# schematics.net
KiCad netlist of a schematic drawn in EAGLE
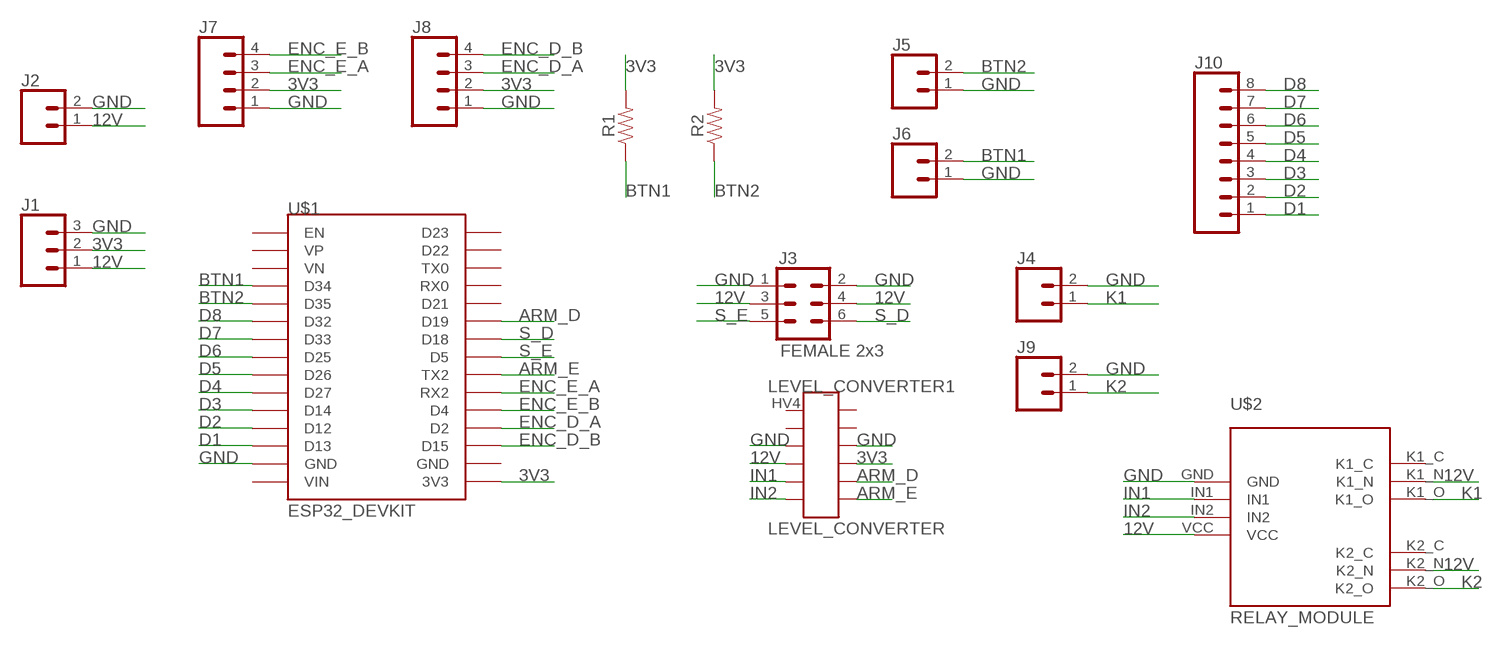
[diagram p0: schematic, sheet 1]

(export (version "E")
  (design (tool "Eeschema 10.0.6"))
  (components
    (comp (ref "J1")
      (value "CONN_03LOCK")
      (footprint "eagle-import:1X03_LOCK")
      (libsource (lib "eagle-import") (part "CONN_03LOCK"))
    )
    (comp (ref "J2")
      (value "CONN_02LOCK")
      (footprint "eagle-import:1X02_LOCK")
      (libsource (lib "eagle-import") (part "CONN_02LOCK"))
    )
    (comp (ref "J3")
      (value "FEMALE 2x3")
      (footprint "eagle-import:2X3")
      (libsource (lib "eagle-import") (part "CONN_03X2FEMALE"))
    )
    (comp (ref "J4")
      (value "CONN_02PTH4")
      (footprint "eagle-import:1X02_XTRA_BIG")
      (libsource (lib "eagle-import") (part "CONN_02PTH4"))
    )
    (comp (ref "J5")
      (value "CONN_02LOCK")
      (footprint "eagle-import:1X02_LOCK")
      (libsource (lib "eagle-import") (part "CONN_02LOCK"))
    )
    (comp (ref "J6")
      (value "CONN_02LOCK")
      (footprint "eagle-import:1X02_LOCK")
      (libsource (lib "eagle-import") (part "CONN_02LOCK"))
    )
    (comp (ref "J7")
      (value "CONN_04LOCK")
      (footprint "eagle-import:1X04_LOCK")
      (libsource (lib "eagle-import") (part "CONN_04LOCK"))
    )
    (comp (ref "J8")
      (value "CONN_04LOCK")
      (footprint "eagle-import:1X04_LOCK")
      (libsource (lib "eagle-import") (part "CONN_04LOCK"))
    )
    (comp (ref "J9")
      (value "CONN_02PTH4")
      (footprint "eagle-import:1X02_XTRA_BIG")
      (libsource (lib "eagle-import") (part "CONN_02PTH4"))
    )
    (comp (ref "J10")
      (value "CONN_08LOCK")
      (footprint "eagle-import:1X08_LOCK")
      (libsource (lib "eagle-import") (part "CONN_08LOCK"))
    )
    (comp (ref "LEVEL_CONVERTER1")
      (value "LEVEL_CONVERTER")
      (footprint "eagle-import:LEVEL_CONVERTER")
      (libsource (lib "eagle-import") (part "LEVEL_CONVERTER"))
    )
    (comp (ref "R1")
      (value "RESISTORAXIAL-0.3")
      (footprint "eagle-import:AXIAL-0.3")
      (libsource (lib "eagle-import") (part "RESISTORAXIAL-0.3"))
    )
    (comp (ref "R2")
      (value "RESISTORAXIAL-0.3")
      (footprint "eagle-import:AXIAL-0.3")
      (libsource (lib "eagle-import") (part "RESISTORAXIAL-0.3"))
    )
    (comp (ref "U$1")
      (value "ESP32_DEVKIT")
      (footprint "eagle-import:ESP32_DEVKIT")
      (libsource (lib "eagle-import") (part "ESP32_DEVKIT"))
    )
    (comp (ref "U$2")
      (value "RELAY_MODULE")
      (footprint "eagle-import:RELAY_MODULE")
      (libsource (lib "eagle-import") (part "RELAY_MODULE"))
    )
  )
  (nets
    (net (code "1") (name "/3V3") (class "Default")
      (node (ref "J1") (pin "2") (pinfunction "2_2") (pintype "passive"))
      (node (ref "J7") (pin "2") (pinfunction "2_2") (pintype "passive"))
      (node (ref "J8") (pin "2") (pinfunction "2_2") (pintype "passive"))
      (node (ref "LEVEL_CONVERTER1") (pin "LV") (pinfunction "LV_LV") (pintype "bidirectional"))
      (node (ref "R1") (pin "P$2") (pinfunction "2_P$2") (pintype "passive"))
      (node (ref "R2") (pin "P$2") (pinfunction "2_P$2") (pintype "passive"))
      (node (ref "U$1") (pin "3V3") (pinfunction "3V3_3V3") (pintype "bidirectional"))
    )
    (net (code "2") (name "/12V") (class "Default")
      (node (ref "J1") (pin "1") (pinfunction "1_1") (pintype "passive"))
      (node (ref "J2") (pin "1") (pinfunction "1_1") (pintype "passive"))
      (node (ref "J3") (pin "3") (pinfunction "3_3") (pintype "bidirectional"))
      (node (ref "J3") (pin "4") (pinfunction "4_4") (pintype "bidirectional"))
      (node (ref "LEVEL_CONVERTER1") (pin "HV") (pinfunction "HV_HV") (pintype "bidirectional"))
      (node (ref "U$2") (pin "K1_N") (pinfunction "K1_N_K1_N") (pintype "bidirectional"))
      (node (ref "U$2") (pin "K2_N") (pinfunction "K2_N_K2_N") (pintype "bidirectional"))
      (node (ref "U$2") (pin "VCC") (pinfunction "VCC_VCC") (pintype "bidirectional"))
    )
    (net (code "3") (name "/ARM_D") (class "Default")
      (node (ref "LEVEL_CONVERTER1") (pin "LV2") (pinfunction "LV2_LV2") (pintype "bidirectional"))
      (node (ref "U$1") (pin "D19") (pinfunction "D19_D19") (pintype "bidirectional"))
    )
    (net (code "4") (name "/ARM_E") (class "Default")
      (node (ref "LEVEL_CONVERTER1") (pin "LV1") (pinfunction "LV1_LV1") (pintype "bidirectional"))
      (node (ref "U$1") (pin "TX2") (pinfunction "TX2_TX2") (pintype "bidirectional"))
    )
    (net (code "5") (name "/BTN1") (class "Default")
      (node (ref "J6") (pin "2") (pinfunction "2_2") (pintype "passive"))
      (node (ref "R1") (pin "P$1") (pinfunction "1_P$1") (pintype "passive"))
      (node (ref "U$1") (pin "D34") (pinfunction "D34_D34") (pintype "bidirectional"))
    )
    (net (code "6") (name "/BTN2") (class "Default")
      (node (ref "J5") (pin "2") (pinfunction "2_2") (pintype "passive"))
      (node (ref "R2") (pin "P$1") (pinfunction "1_P$1") (pintype "passive"))
      (node (ref "U$1") (pin "D35") (pinfunction "D35_D35") (pintype "bidirectional"))
    )
    (net (code "7") (name "/D1") (class "Default")
      (node (ref "J10") (pin "1") (pinfunction "1_1") (pintype "passive"))
      (node (ref "U$1") (pin "D13") (pinfunction "D13_D13") (pintype "bidirectional"))
    )
    (net (code "8") (name "/D2") (class "Default")
      (node (ref "J10") (pin "2") (pinfunction "2_2") (pintype "passive"))
      (node (ref "U$1") (pin "D12") (pinfunction "D12_D12") (pintype "bidirectional"))
    )
    (net (code "9") (name "/D3") (class "Default")
      (node (ref "J10") (pin "3") (pinfunction "3_3") (pintype "passive"))
      (node (ref "U$1") (pin "D14") (pinfunction "D14_D14") (pintype "bidirectional"))
    )
    (net (code "10") (name "/D4") (class "Default")
      (node (ref "J10") (pin "4") (pinfunction "4_4") (pintype "passive"))
      (node (ref "U$1") (pin "D27") (pinfunction "D27_D27") (pintype "bidirectional"))
    )
    (net (code "11") (name "/D5") (class "Default")
      (node (ref "J10") (pin "5") (pinfunction "5_5") (pintype "passive"))
      (node (ref "U$1") (pin "D26") (pinfunction "D26_D26") (pintype "bidirectional"))
    )
    (net (code "12") (name "/D6") (class "Default")
      (node (ref "J10") (pin "6") (pinfunction "6_6") (pintype "passive"))
      (node (ref "U$1") (pin "D25") (pinfunction "D25_D25") (pintype "bidirectional"))
    )
    (net (code "13") (name "/D7") (class "Default")
      (node (ref "J10") (pin "7") (pinfunction "7_7") (pintype "passive"))
      (node (ref "U$1") (pin "D33") (pinfunction "D33_D33") (pintype "bidirectional"))
    )
    (net (code "14") (name "/D8") (class "Default")
      (node (ref "J10") (pin "8") (pinfunction "8_8") (pintype "passive"))
      (node (ref "U$1") (pin "D32") (pinfunction "D32_D32") (pintype "bidirectional"))
    )
    (net (code "15") (name "/ENC_D_A") (class "Default")
      (node (ref "J8") (pin "3") (pinfunction "3_3") (pintype "passive"))
      (node (ref "U$1") (pin "D2") (pinfunction "D2_D2") (pintype "bidirectional"))
    )
    (net (code "16") (name "/ENC_D_B") (class "Default")
      (node (ref "J8") (pin "4") (pinfunction "4_4") (pintype "passive"))
      (node (ref "U$1") (pin "D15") (pinfunction "D15_D15") (pintype "bidirectional"))
    )
    (net (code "17") (name "/ENC_E_A") (class "Default")
      (node (ref "J7") (pin "3") (pinfunction "3_3") (pintype "passive"))
      (node (ref "U$1") (pin "RX2") (pinfunction "RX2_RX2") (pintype "bidirectional"))
    )
    (net (code "18") (name "/ENC_E_B") (class "Default")
      (node (ref "J7") (pin "4") (pinfunction "4_4") (pintype "passive"))
      (node (ref "U$1") (pin "D4") (pinfunction "D4_D4") (pintype "bidirectional"))
    )
    (net (code "19") (name "/GND") (class "Default")
      (node (ref "J1") (pin "3") (pinfunction "3_3") (pintype "passive"))
      (node (ref "J2") (pin "2") (pinfunction "2_2") (pintype "passive"))
      (node (ref "J3") (pin "1") (pinfunction "1_1") (pintype "bidirectional"))
      (node (ref "J3") (pin "2") (pinfunction "2_2") (pintype "bidirectional"))
      (node (ref "J4") (pin "2") (pinfunction "2_2") (pintype "passive"))
      (node (ref "J5") (pin "1") (pinfunction "1_1") (pintype "passive"))
      (node (ref "J6") (pin "1") (pinfunction "1_1") (pintype "passive"))
      (node (ref "J7") (pin "1") (pinfunction "1_1") (pintype "passive"))
      (node (ref "J8") (pin "1") (pinfunction "1_1") (pintype "passive"))
      (node (ref "J9") (pin "2") (pinfunction "2_2") (pintype "passive"))
      (node (ref "LEVEL_CONVERTER1") (pin "GNDH") (pinfunction "GNDH_GNDH") (pintype "bidirectional"))
      (node (ref "LEVEL_CONVERTER1") (pin "GNDL") (pinfunction "GNDL_GNDL") (pintype "bidirectional"))
      (node (ref "U$1") (pin "GND@1") (pinfunction "GND_GND@1") (pintype "bidirectional"))
      (node (ref "U$2") (pin "GND") (pinfunction "GND_GND") (pintype "bidirectional"))
    )
    (net (code "20") (name "/IN1") (class "Default")
      (node (ref "LEVEL_CONVERTER1") (pin "HV2") (pinfunction "HV2_HV2") (pintype "bidirectional"))
      (node (ref "U$2") (pin "IN1") (pinfunction "IN1_IN1") (pintype "bidirectional"))
    )
    (net (code "21") (name "/IN2") (class "Default")
      (node (ref "LEVEL_CONVERTER1") (pin "HV1") (pinfunction "HV1_HV1") (pintype "bidirectional"))
      (node (ref "U$2") (pin "IN2") (pinfunction "IN2_IN2") (pintype "bidirectional"))
    )
    (net (code "22") (name "/K1") (class "Default")
      (node (ref "J4") (pin "1") (pinfunction "1_1") (pintype "passive"))
      (node (ref "U$2") (pin "K1_O") (pinfunction "K1_O_K1_O") (pintype "bidirectional"))
    )
    (net (code "23") (name "/K2") (class "Default")
      (node (ref "J9") (pin "1") (pinfunction "1_1") (pintype "passive"))
      (node (ref "U$2") (pin "K2_O") (pinfunction "K2_O_K2_O") (pintype "bidirectional"))
    )
    (net (code "24") (name "/S_D") (class "Default")
      (node (ref "J3") (pin "6") (pinfunction "6_6") (pintype "bidirectional"))
      (node (ref "U$1") (pin "D18") (pinfunction "D18_D18") (pintype "bidirectional"))
    )
    (net (code "25") (name "/S_E") (class "Default")
      (node (ref "J3") (pin "5") (pinfunction "5_5") (pintype "bidirectional"))
      (node (ref "U$1") (pin "D5") (pinfunction "D5_D5") (pintype "bidirectional"))
    )
    (net (code "26") (name "unconnected-(LEVEL_CONVERTER1-PadHV3)") (class "Default")
      (node (ref "LEVEL_CONVERTER1") (pin "HV3") (pinfunction "HV3_HV3") (pintype "bidirectional"))
    )
    (net (code "27") (name "unconnected-(LEVEL_CONVERTER1-PadHV4)") (class "Default")
      (node (ref "LEVEL_CONVERTER1") (pin "HV4") (pinfunction "HV4_HV4") (pintype "bidirectional"))
    )
    (net (code "28") (name "unconnected-(LEVEL_CONVERTER1-PadLV3)") (class "Default")
      (node (ref "LEVEL_CONVERTER1") (pin "LV3") (pinfunction "LV3_LV3") (pintype "bidirectional"))
    )
    (net (code "29") (name "unconnected-(LEVEL_CONVERTER1-PadLV4)") (class "Default")
      (node (ref "LEVEL_CONVERTER1") (pin "LV4") (pinfunction "LV4_LV4") (pintype "bidirectional"))
    )
    (net (code "30") (name "unconnected-(U$1-GND-PadGND@2)") (class "Default")
      (node (ref "U$1") (pin "GND@2") (pinfunction "GND_GND@2") (pintype "bidirectional"))
    )
    (net (code "31") (name "unconnected-(U$1-PadD21)") (class "Default")
      (node (ref "U$1") (pin "D21") (pinfunction "D21_D21") (pintype "bidirectional"))
    )
    (net (code "32") (name "unconnected-(U$1-PadD22)") (class "Default")
      (node (ref "U$1") (pin "D22") (pinfunction "D22_D22") (pintype "bidirectional"))
    )
    (net (code "33") (name "unconnected-(U$1-PadD23)") (class "Default")
      (node (ref "U$1") (pin "D23") (pinfunction "D23_D23") (pintype "bidirectional"))
    )
    (net (code "34") (name "unconnected-(U$1-PadEN)") (class "Default")
      (node (ref "U$1") (pin "EN") (pinfunction "EN_EN") (pintype "bidirectional"))
    )
    (net (code "35") (name "unconnected-(U$1-PadRX0)") (class "Default")
      (node (ref "U$1") (pin "RX0") (pinfunction "RX0_RX0") (pintype "bidirectional"))
    )
    (net (code "36") (name "unconnected-(U$1-PadTX0)") (class "Default")
      (node (ref "U$1") (pin "TX0") (pinfunction "TX0_TX0") (pintype "bidirectional"))
    )
    (net (code "37") (name "unconnected-(U$1-PadVIN)") (class "Default")
      (node (ref "U$1") (pin "VIN") (pinfunction "VIN_VIN") (pintype "bidirectional"))
    )
    (net (code "38") (name "unconnected-(U$1-PadVN)") (class "Default")
      (node (ref "U$1") (pin "VN") (pinfunction "VN_VN") (pintype "bidirectional"))
    )
    (net (code "39") (name "unconnected-(U$1-PadVP)") (class "Default")
      (node (ref "U$1") (pin "VP") (pinfunction "VP_VP") (pintype "bidirectional"))
    )
    (net (code "40") (name "unconnected-(U$2-PadK1_C)") (class "Default")
      (node (ref "U$2") (pin "K1_C") (pinfunction "K1_C_K1_C") (pintype "bidirectional"))
    )
    (net (code "41") (name "unconnected-(U$2-PadK2_C)") (class "Default")
      (node (ref "U$2") (pin "K2_C") (pinfunction "K2_C_K2_C") (pintype "bidirectional"))
    )
  )
)
